# BaseModule.net
KiCad netlist of a schematic drawn in EAGLE
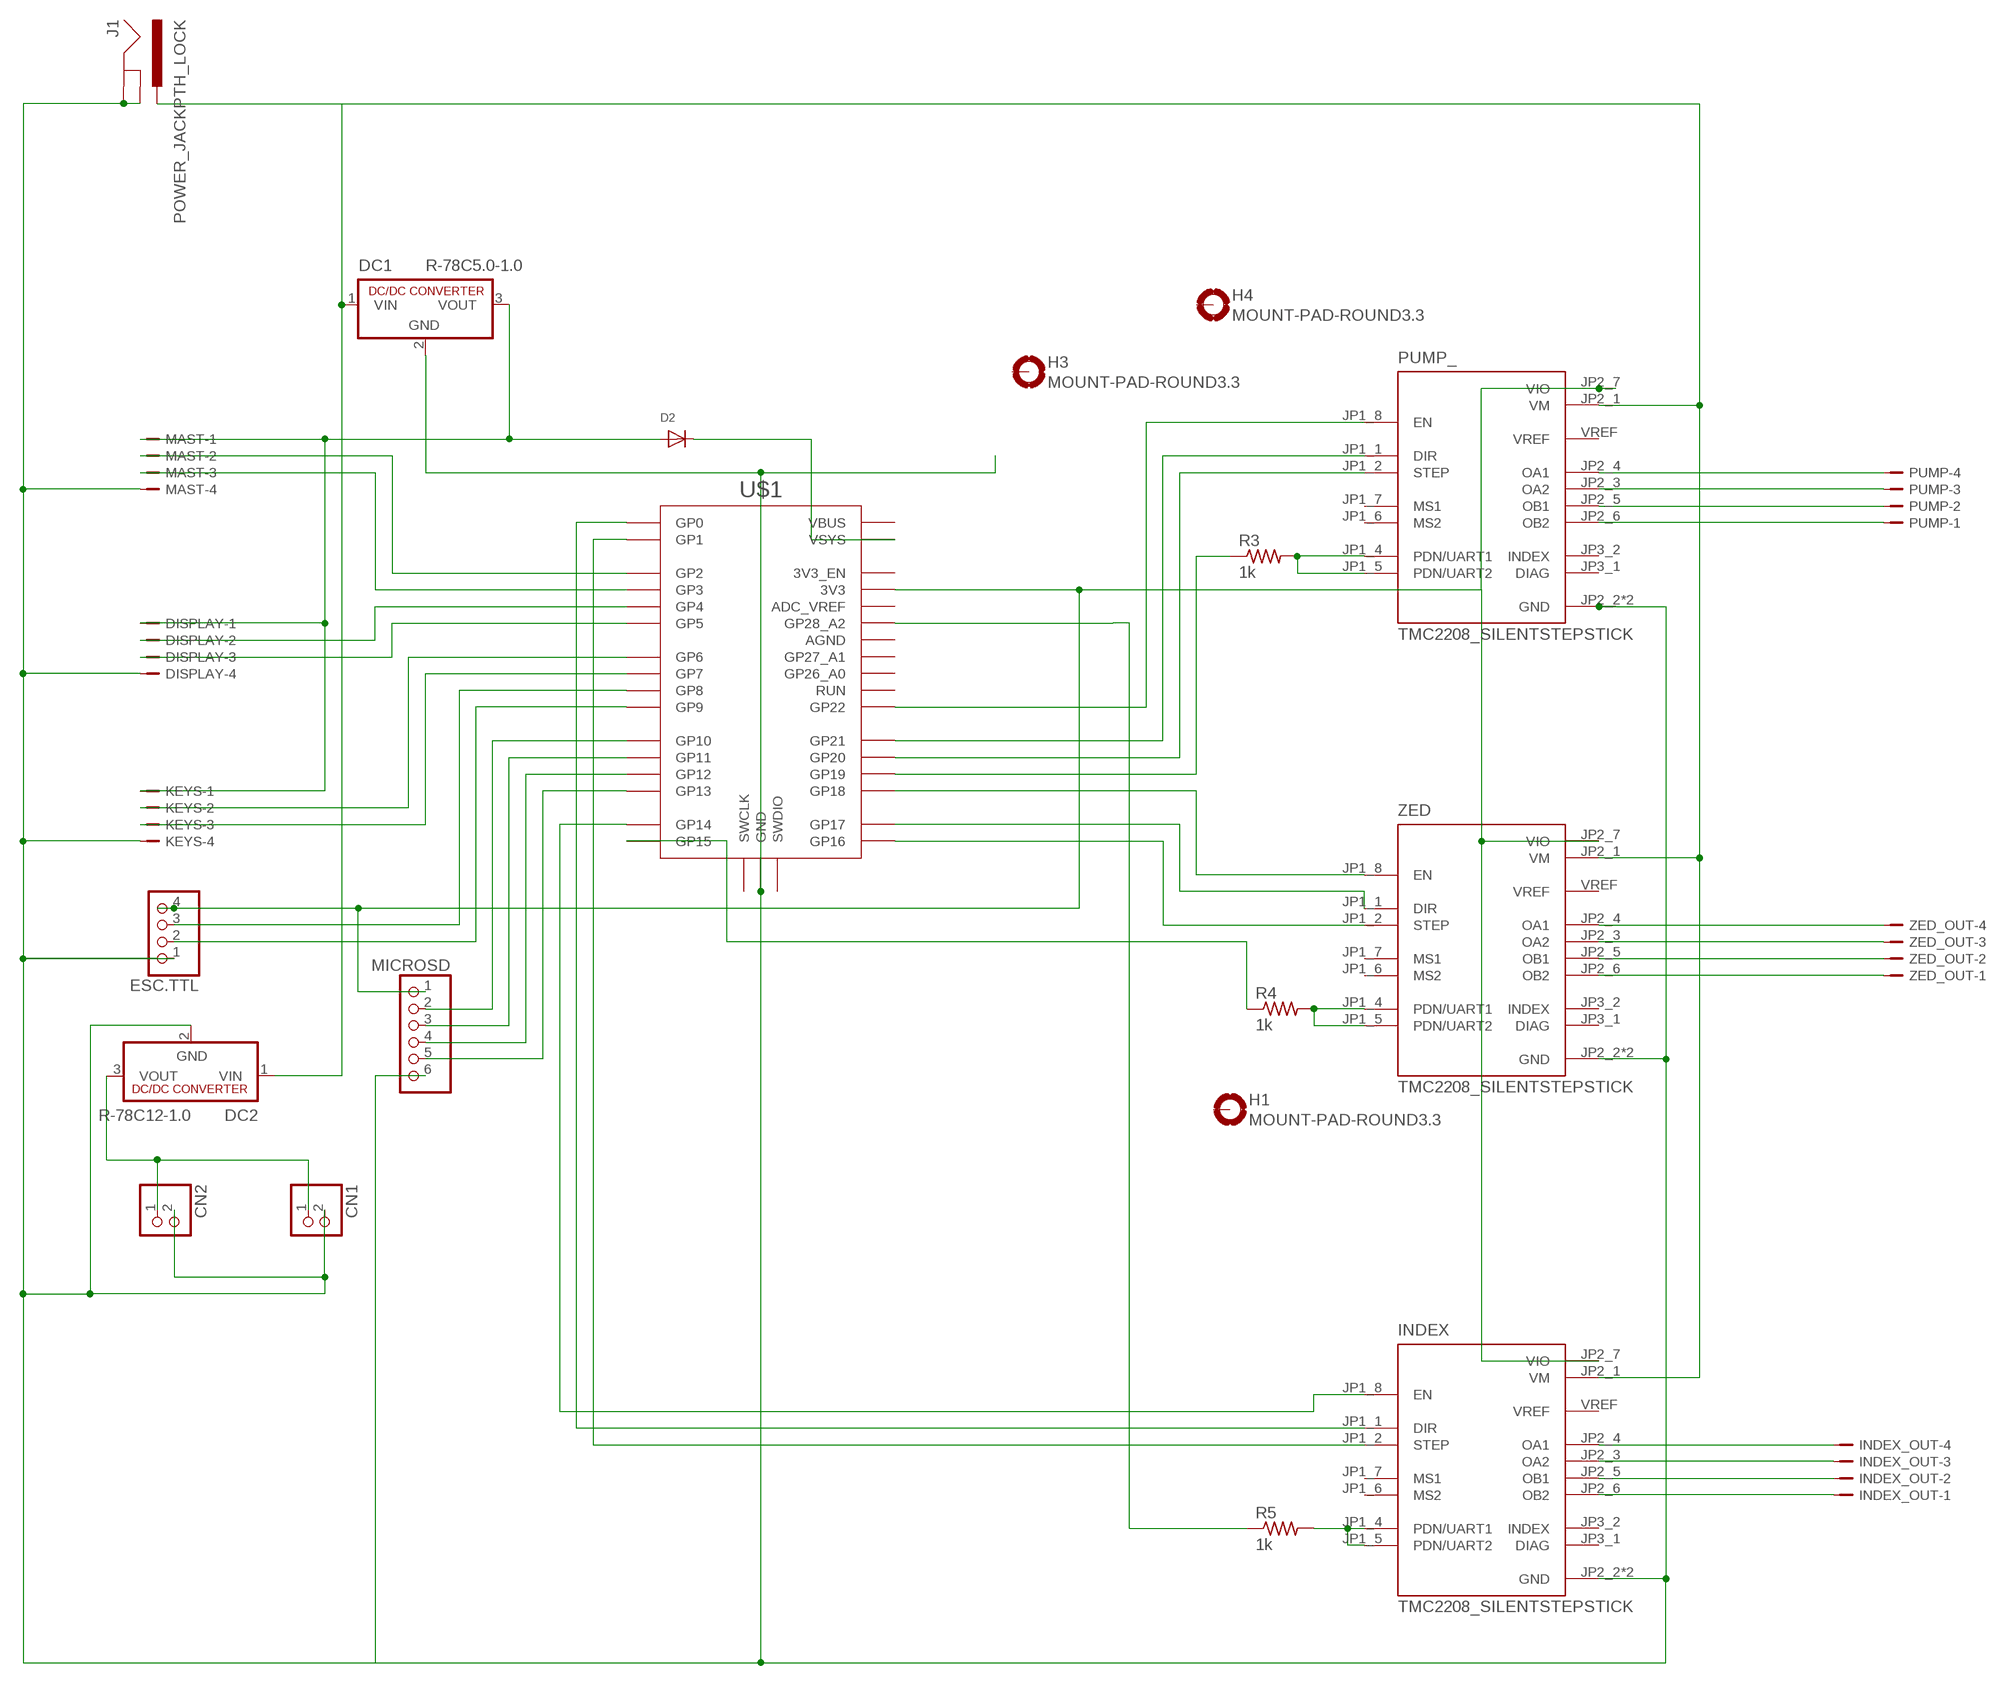
[diagram p0: schematic, sheet 1]

(export (version "E")
  (design (tool "Eeschema 10.0.6"))
  (components
    (comp (ref "CN1")
      (value "JST_2PIN-THM-RA")
      (footprint "eagle-import:JST-PH-2-THM-RA")
      (libsource (lib "eagle-import") (part "JST_2PIN-THM-RA"))
    )
    (comp (ref "CN2")
      (value "JST_2PIN-THM-RA")
      (footprint "eagle-import:JST-PH-2-THM-RA")
      (libsource (lib "eagle-import") (part "JST_2PIN-THM-RA"))
    )
    (comp (ref "D2")
      (value "DIODESMA")
      (footprint "eagle-import:SMADIODE")
      (libsource (lib "eagle-import") (part "DIODESMA"))
    )
    (comp (ref "DC1")
      (value "R-78C5.0-1.0")
      (footprint "eagle-import:SIP3")
      (libsource (lib "eagle-import") (part "R-78C-1.05.0"))
    )
    (comp (ref "DC2")
      (value "R-78C12-1.0")
      (footprint "eagle-import:SIP3")
      (libsource (lib "eagle-import") (part "R-78C-1.012"))
    )
    (comp (ref "DISPLAY")
      (value "JST-PH-4_TH-V")
      (footprint "eagle-import:B4B-PH-K-S")
      (fields (field (name "MF") "JST") (field (name "MPN") "B4B-PH-K-S"))
      (libsource (lib "eagle-import") (part "JST-PH-4_TH-V"))
    )
    (comp (ref "ESC.TTL")
      (value "PINHD-1X4")
      (footprint "eagle-import:1X04")
      (libsource (lib "eagle-import") (part "PINHD-1X4"))
    )
    (comp (ref "H1")
      (value "MOUNT-PAD-ROUND3.3")
      (footprint "eagle-import:3,3-PAD")
      (libsource (lib "eagle-import") (part "MOUNT-PAD-ROUND3.3"))
    )
    (comp (ref "H3")
      (value "MOUNT-PAD-ROUND3.3")
      (footprint "eagle-import:3,3-PAD")
      (libsource (lib "eagle-import") (part "MOUNT-PAD-ROUND3.3"))
    )
    (comp (ref "H4")
      (value "MOUNT-PAD-ROUND3.3")
      (footprint "eagle-import:3,3-PAD")
      (libsource (lib "eagle-import") (part "MOUNT-PAD-ROUND3.3"))
    )
    (comp (ref "INDEX")
      (value "TMC2208_SILENTSTEPSTICK")
      (footprint "eagle-import:MODULE_TMC2208_SILENTSTEPSTICK")
      (fields (field (name "MF") "Trinamic Motion") (field (name "MP") "TMC2208 SILENTSTEPSTICK"))
      (libsource (lib "eagle-import") (part "TMC2208_SILENTSTEPSTICK"))
    )
    (comp (ref "INDEX_OUT")
      (value "JST-PH-4_TH-RA")
      (footprint "eagle-import:S4B-PH-KL")
      (fields (field (name "MF") "JST") (field (name "MPN") "S4B-PH-KL"))
      (libsource (lib "eagle-import") (part "JST-PH-4_TH-RA"))
    )
    (comp (ref "J1")
      (value "POWER_JACKPTH_LOCK")
      (footprint "eagle-import:POWER_JACK_PTH_LOCK")
      (libsource (lib "eagle-import") (part "POWER_JACKPTH_LOCK"))
    )
    (comp (ref "KEYS")
      (value "JST-PH-4_TH-V")
      (footprint "eagle-import:B4B-PH-K-S")
      (fields (field (name "MF") "JST") (field (name "MPN") "B4B-PH-K-S"))
      (libsource (lib "eagle-import") (part "JST-PH-4_TH-V"))
    )
    (comp (ref "MAST")
      (value "JST-PH-4_TH-V")
      (footprint "eagle-import:B4B-PH-K-S")
      (fields (field (name "MF") "JST") (field (name "MPN") "B4B-PH-K-S"))
      (libsource (lib "eagle-import") (part "JST-PH-4_TH-V"))
    )
    (comp (ref "MICROSD")
      (value "PINHD-1X6")
      (footprint "eagle-import:1X06")
      (libsource (lib "eagle-import") (part "PINHD-1X6"))
    )
    (comp (ref "PUMP")
      (value "JST-PH-4_TH-RA")
      (footprint "eagle-import:S4B-PH-KL")
      (fields (field (name "MF") "JST") (field (name "MPN") "S4B-PH-KL"))
      (libsource (lib "eagle-import") (part "JST-PH-4_TH-RA"))
    )
    (comp (ref "PUMP_")
      (value "TMC2208_SILENTSTEPSTICK")
      (footprint "eagle-import:MODULE_TMC2208_SILENTSTEPSTICK")
      (fields (field (name "MF") "Trinamic Motion") (field (name "MP") "TMC2208 SILENTSTEPSTICK"))
      (libsource (lib "eagle-import") (part "TMC2208_SILENTSTEPSTICK"))
    )
    (comp (ref "R3")
      (value "1k")
      (footprint "eagle-import:R1206")
      (libsource (lib "eagle-import") (part "R-US_R1206"))
    )
    (comp (ref "R4")
      (value "1k")
      (footprint "eagle-import:R1206")
      (libsource (lib "eagle-import") (part "R-US_R1206"))
    )
    (comp (ref "R5")
      (value "1k")
      (footprint "eagle-import:R1206")
      (libsource (lib "eagle-import") (part "R-US_R1206"))
    )
    (comp (ref "U$1")
      (value "RPI_PICO-TH")
      (footprint "eagle-import:RPI_PICO_TH")
      (libsource (lib "eagle-import") (part "RPI_PICO-TH"))
    )
    (comp (ref "ZED")
      (value "TMC2208_SILENTSTEPSTICK")
      (footprint "eagle-import:MODULE_TMC2208_SILENTSTEPSTICK")
      (fields (field (name "MF") "Trinamic Motion") (field (name "MP") "TMC2208 SILENTSTEPSTICK"))
      (libsource (lib "eagle-import") (part "TMC2208_SILENTSTEPSTICK"))
    )
    (comp (ref "ZED_OUT")
      (value "JST-PH-4_TH-RA")
      (footprint "eagle-import:S4B-PH-KL")
      (fields (field (name "MF") "JST") (field (name "MPN") "S4B-PH-KL"))
      (libsource (lib "eagle-import") (part "JST-PH-4_TH-RA"))
    )
  )
  (nets
    (net (code "1") (name "Net-(CN1-1)") (class "Default")
      (node (ref "CN1") (pin "2") (pinfunction "1_2") (pintype "passive"))
      (node (ref "CN2") (pin "2") (pinfunction "1_2") (pintype "passive"))
      (node (ref "DC1") (pin "2") (pinfunction "GND_2") (pintype "passive"))
      (node (ref "DC2") (pin "2") (pinfunction "GND_2") (pintype "passive"))
      (node (ref "DISPLAY") (pin "4") (pinfunction "1_4") (pintype "passive"))
      (node (ref "ESC.TTL") (pin "1") (pinfunction "1_1") (pintype "passive"))
      (node (ref "INDEX") (pin "JP2_2") (pinfunction "GND_JP2_2") (pintype "power_in"))
      (node (ref "INDEX") (pin "JP2_8") (pinfunction "GND_JP2_8") (pintype "power_in"))
      (node (ref "J1") (pin "GND") (pinfunction "GND_GND") (pintype "bidirectional"))
      (node (ref "J1") (pin "GNDBREAK") (pinfunction "GNDBREAK_GNDBREAK") (pintype "bidirectional"))
      (node (ref "KEYS") (pin "4") (pinfunction "1_4") (pintype "passive"))
      (node (ref "MAST") (pin "4") (pinfunction "1_4") (pintype "passive"))
      (node (ref "MICROSD") (pin "6") (pinfunction "6_6") (pintype "passive"))
      (node (ref "PUMP_") (pin "JP2_2") (pinfunction "GND_JP2_2") (pintype "power_in"))
      (node (ref "PUMP_") (pin "JP2_8") (pinfunction "GND_JP2_8") (pintype "power_in"))
      (node (ref "U$1") (pin "GND@1") (pinfunction "GND_GND@1") (pintype "bidirectional"))
      (node (ref "U$1") (pin "GND@2") (pinfunction "GND_GND@2") (pintype "bidirectional"))
      (node (ref "U$1") (pin "GND@3") (pinfunction "GND_GND@3") (pintype "bidirectional"))
      (node (ref "U$1") (pin "GND@4") (pinfunction "GND_GND@4") (pintype "bidirectional"))
      (node (ref "U$1") (pin "GND@5") (pinfunction "GND_GND@5") (pintype "bidirectional"))
      (node (ref "U$1") (pin "GND@6") (pinfunction "GND_GND@6") (pintype "bidirectional"))
      (node (ref "U$1") (pin "GND@7") (pinfunction "GND_GND@7") (pintype "bidirectional"))
      (node (ref "U$1") (pin "GND@8") (pinfunction "GND_GND@8") (pintype "bidirectional"))
      (node (ref "ZED") (pin "JP2_2") (pinfunction "GND_JP2_2") (pintype "power_in"))
      (node (ref "ZED") (pin "JP2_8") (pinfunction "GND_JP2_8") (pintype "power_in"))
    )
    (net (code "2") (name "Net-(CN1-2)") (class "Default")
      (node (ref "CN1") (pin "1") (pinfunction "2_1") (pintype "passive"))
      (node (ref "CN2") (pin "1") (pinfunction "2_1") (pintype "passive"))
      (node (ref "DC2") (pin "3") (pinfunction "VOUT_3") (pintype "passive"))
    )
    (net (code "3") (name "Net-(D2-PadC)") (class "Default")
      (node (ref "D2") (pin "C") (pinfunction "C_C") (pintype "passive"))
      (node (ref "U$1") (pin "VSYS") (pinfunction "VSYS_VSYS") (pintype "bidirectional"))
    )
    (net (code "4") (name "Net-(DC1-VIN)") (class "Default")
      (node (ref "DC1") (pin "1") (pinfunction "VIN_1") (pintype "passive"))
      (node (ref "DC2") (pin "1") (pinfunction "VIN_1") (pintype "passive"))
      (node (ref "INDEX") (pin "JP2_1") (pinfunction "VM_JP2_1") (pintype "power_in"))
      (node (ref "J1") (pin "PWR") (pinfunction "PWR_PWR") (pintype "bidirectional"))
      (node (ref "PUMP_") (pin "JP2_1") (pinfunction "VM_JP2_1") (pintype "power_in"))
      (node (ref "ZED") (pin "JP2_1") (pinfunction "VM_JP2_1") (pintype "power_in"))
    )
    (net (code "5") (name "Net-(DC1-VOUT)") (class "Default")
      (node (ref "D2") (pin "A") (pinfunction "A_A") (pintype "passive"))
      (node (ref "DC1") (pin "3") (pinfunction "VOUT_3") (pintype "passive"))
      (node (ref "DISPLAY") (pin "1") (pinfunction "1_1") (pintype "passive"))
      (node (ref "KEYS") (pin "1") (pinfunction "1_1") (pintype "passive"))
      (node (ref "MAST") (pin "1") (pinfunction "1_1") (pintype "passive"))
    )
    (net (code "6") (name "Net-(DISPLAYB-1)") (class "Default")
      (node (ref "DISPLAY") (pin "2") (pinfunction "1_2") (pintype "passive"))
      (node (ref "U$1") (pin "GP4") (pinfunction "GP4_GP4") (pintype "bidirectional"))
    )
    (net (code "7") (name "Net-(DISPLAYC-1)") (class "Default")
      (node (ref "DISPLAY") (pin "3") (pinfunction "1_3") (pintype "passive"))
      (node (ref "U$1") (pin "GP5") (pinfunction "GP5_GP5") (pintype "bidirectional"))
    )
    (net (code "8") (name "Net-(ESC.TTL-Pad2)") (class "Default")
      (node (ref "ESC.TTL") (pin "2") (pinfunction "2_2") (pintype "passive"))
      (node (ref "U$1") (pin "GP9") (pinfunction "GP9_GP9") (pintype "bidirectional"))
    )
    (net (code "9") (name "Net-(ESC.TTL-Pad3)") (class "Default")
      (node (ref "ESC.TTL") (pin "3") (pinfunction "3_3") (pintype "passive"))
      (node (ref "U$1") (pin "GP8") (pinfunction "GP8_GP8") (pintype "bidirectional"))
    )
    (net (code "10") (name "Net-(INDEX-DIR)") (class "Default")
      (node (ref "INDEX") (pin "JP1_1") (pinfunction "DIR_JP1_1") (pintype "input"))
      (node (ref "U$1") (pin "GP0") (pinfunction "GP0_GP0") (pintype "bidirectional"))
    )
    (net (code "11") (name "Net-(INDEX-EN)") (class "Default")
      (node (ref "INDEX") (pin "JP1_8") (pinfunction "EN_JP1_8") (pintype "input"))
      (node (ref "U$1") (pin "GP14") (pinfunction "GP14_GP14") (pintype "bidirectional"))
    )
    (net (code "12") (name "Net-(INDEX-OA1)") (class "Default")
      (node (ref "INDEX") (pin "JP2_4") (pinfunction "OA1_JP2_4") (pintype "passive"))
      (node (ref "INDEX_OUT") (pin "4") (pinfunction "1_4") (pintype "passive"))
    )
    (net (code "13") (name "Net-(INDEX-OA2)") (class "Default")
      (node (ref "INDEX") (pin "JP2_3") (pinfunction "OA2_JP2_3") (pintype "passive"))
      (node (ref "INDEX_OUT") (pin "3") (pinfunction "1_3") (pintype "passive"))
    )
    (net (code "14") (name "Net-(INDEX-OB1)") (class "Default")
      (node (ref "INDEX") (pin "JP2_5") (pinfunction "OB1_JP2_5") (pintype "passive"))
      (node (ref "INDEX_OUT") (pin "2") (pinfunction "1_2") (pintype "passive"))
    )
    (net (code "15") (name "Net-(INDEX-OB2)") (class "Default")
      (node (ref "INDEX") (pin "JP2_6") (pinfunction "OB2_JP2_6") (pintype "passive"))
      (node (ref "INDEX_OUT") (pin "1") (pinfunction "1_1") (pintype "passive"))
    )
    (net (code "16") (name "Net-(INDEX-PDN{slash}UART1)") (class "Default")
      (node (ref "INDEX") (pin "JP1_4") (pinfunction "PDN/UART1_JP1_4") (pintype "bidirectional"))
      (node (ref "INDEX") (pin "JP1_5") (pinfunction "PDN/UART2_JP1_5") (pintype "bidirectional"))
      (node (ref "R5") (pin "2") (pinfunction "2_2") (pintype "passive"))
    )
    (net (code "17") (name "Net-(INDEX-STEP)") (class "Default")
      (node (ref "INDEX") (pin "JP1_2") (pinfunction "STEP_JP1_2") (pintype "input"))
      (node (ref "U$1") (pin "GP1") (pinfunction "GP1_GP1") (pintype "bidirectional"))
    )
    (net (code "18") (name "Net-(INDEX-VIO)") (class "Default")
      (node (ref "ESC.TTL") (pin "4") (pinfunction "4_4") (pintype "passive"))
      (node (ref "INDEX") (pin "JP2_7") (pinfunction "VIO_JP2_7") (pintype "power_in"))
      (node (ref "MICROSD") (pin "1") (pinfunction "1_1") (pintype "passive"))
      (node (ref "PUMP_") (pin "JP2_7") (pinfunction "VIO_JP2_7") (pintype "power_in"))
      (node (ref "U$1") (pin "3V3") (pinfunction "3V3_3V3") (pintype "bidirectional"))
      (node (ref "ZED") (pin "JP2_7") (pinfunction "VIO_JP2_7") (pintype "power_in"))
    )
    (net (code "19") (name "Net-(KEYSB-1)") (class "Default")
      (node (ref "KEYS") (pin "2") (pinfunction "1_2") (pintype "passive"))
      (node (ref "U$1") (pin "GP6") (pinfunction "GP6_GP6") (pintype "bidirectional"))
    )
    (net (code "20") (name "Net-(KEYSC-1)") (class "Default")
      (node (ref "KEYS") (pin "3") (pinfunction "1_3") (pintype "passive"))
      (node (ref "U$1") (pin "GP7") (pinfunction "GP7_GP7") (pintype "bidirectional"))
    )
    (net (code "21") (name "Net-(MASTB-1)") (class "Default")
      (node (ref "MAST") (pin "2") (pinfunction "1_2") (pintype "passive"))
      (node (ref "U$1") (pin "GP2") (pinfunction "GP2_GP2") (pintype "bidirectional"))
    )
    (net (code "22") (name "Net-(MASTC-1)") (class "Default")
      (node (ref "MAST") (pin "3") (pinfunction "1_3") (pintype "passive"))
      (node (ref "U$1") (pin "GP3") (pinfunction "GP3_GP3") (pintype "bidirectional"))
    )
    (net (code "23") (name "Net-(MICROSD-Pad2)") (class "Default")
      (node (ref "MICROSD") (pin "2") (pinfunction "2_2") (pintype "passive"))
      (node (ref "U$1") (pin "GP10") (pinfunction "GP10_GP10") (pintype "bidirectional"))
    )
    (net (code "24") (name "Net-(MICROSD-Pad3)") (class "Default")
      (node (ref "MICROSD") (pin "3") (pinfunction "3_3") (pintype "passive"))
      (node (ref "U$1") (pin "GP11") (pinfunction "GP11_GP11") (pintype "bidirectional"))
    )
    (net (code "25") (name "Net-(MICROSD-Pad4)") (class "Default")
      (node (ref "MICROSD") (pin "4") (pinfunction "4_4") (pintype "passive"))
      (node (ref "U$1") (pin "GP12") (pinfunction "GP12_GP12") (pintype "bidirectional"))
    )
    (net (code "26") (name "Net-(MICROSD-Pad5)") (class "Default")
      (node (ref "MICROSD") (pin "5") (pinfunction "5_5") (pintype "passive"))
      (node (ref "U$1") (pin "GP13") (pinfunction "GP13_GP13") (pintype "bidirectional"))
    )
    (net (code "27") (name "Net-(PUMPB-1)") (class "Default")
      (node (ref "PUMP") (pin "2") (pinfunction "1_2") (pintype "passive"))
      (node (ref "PUMP_") (pin "JP2_5") (pinfunction "OB1_JP2_5") (pintype "passive"))
    )
    (net (code "28") (name "Net-(PUMPC-1)") (class "Default")
      (node (ref "PUMP") (pin "3") (pinfunction "1_3") (pintype "passive"))
      (node (ref "PUMP_") (pin "JP2_3") (pinfunction "OA2_JP2_3") (pintype "passive"))
    )
    (net (code "29") (name "Net-(PUMPD-1)") (class "Default")
      (node (ref "PUMP") (pin "4") (pinfunction "1_4") (pintype "passive"))
      (node (ref "PUMP_") (pin "JP2_4") (pinfunction "OA1_JP2_4") (pintype "passive"))
    )
    (net (code "30") (name "Net-(PUMP_-DIR)") (class "Default")
      (node (ref "PUMP_") (pin "JP1_1") (pinfunction "DIR_JP1_1") (pintype "input"))
      (node (ref "U$1") (pin "GP21") (pinfunction "GP21_GP21") (pintype "bidirectional"))
    )
    (net (code "31") (name "Net-(PUMP_-EN)") (class "Default")
      (node (ref "PUMP_") (pin "JP1_8") (pinfunction "EN_JP1_8") (pintype "input"))
      (node (ref "U$1") (pin "GP22") (pinfunction "GP22_GP22") (pintype "bidirectional"))
    )
    (net (code "32") (name "Net-(PUMP_-OB2)") (class "Default")
      (node (ref "PUMP") (pin "1") (pinfunction "1_1") (pintype "passive"))
      (node (ref "PUMP_") (pin "JP2_6") (pinfunction "OB2_JP2_6") (pintype "passive"))
    )
    (net (code "33") (name "Net-(PUMP_-PDN{slash}UART1)") (class "Default")
      (node (ref "PUMP_") (pin "JP1_4") (pinfunction "PDN/UART1_JP1_4") (pintype "bidirectional"))
      (node (ref "PUMP_") (pin "JP1_5") (pinfunction "PDN/UART2_JP1_5") (pintype "bidirectional"))
      (node (ref "R3") (pin "2") (pinfunction "2_2") (pintype "passive"))
    )
    (net (code "34") (name "Net-(PUMP_-STEP)") (class "Default")
      (node (ref "PUMP_") (pin "JP1_2") (pinfunction "STEP_JP1_2") (pintype "input"))
      (node (ref "U$1") (pin "GP20") (pinfunction "GP20_GP20") (pintype "bidirectional"))
    )
    (net (code "35") (name "Net-(R3-Pad1)") (class "Default")
      (node (ref "R3") (pin "1") (pinfunction "1_1") (pintype "passive"))
      (node (ref "U$1") (pin "GP19") (pinfunction "GP19_GP19") (pintype "bidirectional"))
    )
    (net (code "36") (name "Net-(R4-Pad1)") (class "Default")
      (node (ref "R4") (pin "1") (pinfunction "1_1") (pintype "passive"))
      (node (ref "U$1") (pin "GP15") (pinfunction "GP15_GP15") (pintype "bidirectional"))
    )
    (net (code "37") (name "Net-(R5-Pad1)") (class "Default")
      (node (ref "R5") (pin "1") (pinfunction "1_1") (pintype "passive"))
      (node (ref "U$1") (pin "GP28_A2") (pinfunction "GP28_A2_GP28_A2") (pintype "bidirectional"))
    )
    (net (code "38") (name "Net-(ZED-DIR)") (class "Default")
      (node (ref "U$1") (pin "GP17") (pinfunction "GP17_GP17") (pintype "bidirectional"))
      (node (ref "ZED") (pin "JP1_1") (pinfunction "DIR_JP1_1") (pintype "input"))
    )
    (net (code "39") (name "Net-(ZED-EN)") (class "Default")
      (node (ref "U$1") (pin "GP18") (pinfunction "GP18_GP18") (pintype "bidirectional"))
      (node (ref "ZED") (pin "JP1_8") (pinfunction "EN_JP1_8") (pintype "input"))
    )
    (net (code "40") (name "Net-(ZED-OA1)") (class "Default")
      (node (ref "ZED") (pin "JP2_4") (pinfunction "OA1_JP2_4") (pintype "passive"))
      (node (ref "ZED_OUT") (pin "4") (pinfunction "1_4") (pintype "passive"))
    )
    (net (code "41") (name "Net-(ZED-OA2)") (class "Default")
      (node (ref "ZED") (pin "JP2_3") (pinfunction "OA2_JP2_3") (pintype "passive"))
      (node (ref "ZED_OUT") (pin "3") (pinfunction "1_3") (pintype "passive"))
    )
    (net (code "42") (name "Net-(ZED-OB1)") (class "Default")
      (node (ref "ZED") (pin "JP2_5") (pinfunction "OB1_JP2_5") (pintype "passive"))
      (node (ref "ZED_OUT") (pin "2") (pinfunction "1_2") (pintype "passive"))
    )
    (net (code "43") (name "Net-(ZED-OB2)") (class "Default")
      (node (ref "ZED") (pin "JP2_6") (pinfunction "OB2_JP2_6") (pintype "passive"))
      (node (ref "ZED_OUT") (pin "1") (pinfunction "1_1") (pintype "passive"))
    )
    (net (code "44") (name "Net-(ZED-PDN{slash}UART1)") (class "Default")
      (node (ref "R4") (pin "2") (pinfunction "2_2") (pintype "passive"))
      (node (ref "ZED") (pin "JP1_4") (pinfunction "PDN/UART1_JP1_4") (pintype "bidirectional"))
      (node (ref "ZED") (pin "JP1_5") (pinfunction "PDN/UART2_JP1_5") (pintype "bidirectional"))
    )
    (net (code "45") (name "Net-(ZED-STEP)") (class "Default")
      (node (ref "U$1") (pin "GP16") (pinfunction "GP16_GP16") (pintype "bidirectional"))
      (node (ref "ZED") (pin "JP1_2") (pinfunction "STEP_JP1_2") (pintype "input"))
    )
    (net (code "46") (name "unconnected-(H1-MOUNT-PadB3,3)") (class "Default")
      (node (ref "H1") (pin "B3,3") (pinfunction "MOUNT_B3,3") (pintype "passive"))
    )
    (net (code "47") (name "unconnected-(H3-MOUNT-PadB3,3)") (class "Default")
      (node (ref "H3") (pin "B3,3") (pinfunction "MOUNT_B3,3") (pintype "passive"))
    )
    (net (code "48") (name "unconnected-(H4-MOUNT-PadB3,3)") (class "Default")
      (node (ref "H4") (pin "B3,3") (pinfunction "MOUNT_B3,3") (pintype "passive"))
    )
    (net (code "49") (name "unconnected-(INDEX-DIAG-PadJP3_1)") (class "Default")
      (node (ref "INDEX") (pin "JP3_1") (pinfunction "DIAG_JP3_1") (pintype "output"))
    )
    (net (code "50") (name "unconnected-(INDEX-INDEX-PadJP3_2)") (class "Default")
      (node (ref "INDEX") (pin "JP3_2") (pinfunction "INDEX_JP3_2") (pintype "output"))
    )
    (net (code "51") (name "unconnected-(INDEX-MS1-PadJP1_7)") (class "Default")
      (node (ref "INDEX") (pin "JP1_7") (pinfunction "MS1_JP1_7") (pintype "input"))
    )
    (net (code "52") (name "unconnected-(INDEX-MS2-PadJP1_6)") (class "Default")
      (node (ref "INDEX") (pin "JP1_6") (pinfunction "MS2_JP1_6") (pintype "input"))
    )
    (net (code "53") (name "unconnected-(INDEX-PadVREF)") (class "Default")
      (node (ref "INDEX") (pin "VREF") (pinfunction "VREF_VREF") (pintype "passive"))
    )
    (net (code "54") (name "unconnected-(PUMP_-DIAG-PadJP3_1)") (class "Default")
      (node (ref "PUMP_") (pin "JP3_1") (pinfunction "DIAG_JP3_1") (pintype "output"))
    )
    (net (code "55") (name "unconnected-(PUMP_-INDEX-PadJP3_2)") (class "Default")
      (node (ref "PUMP_") (pin "JP3_2") (pinfunction "INDEX_JP3_2") (pintype "output"))
    )
    (net (code "56") (name "unconnected-(PUMP_-MS1-PadJP1_7)") (class "Default")
      (node (ref "PUMP_") (pin "JP1_7") (pinfunction "MS1_JP1_7") (pintype "input"))
    )
    (net (code "57") (name "unconnected-(PUMP_-MS2-PadJP1_6)") (class "Default")
      (node (ref "PUMP_") (pin "JP1_6") (pinfunction "MS2_JP1_6") (pintype "input"))
    )
    (net (code "58") (name "unconnected-(PUMP_-PadVREF)") (class "Default")
      (node (ref "PUMP_") (pin "VREF") (pinfunction "VREF_VREF") (pintype "passive"))
    )
    (net (code "59") (name "unconnected-(U$1-Pad3V3_EN)") (class "Default")
      (node (ref "U$1") (pin "3V3_EN") (pinfunction "3V3_EN_3V3_EN") (pintype "bidirectional"))
    )
    (net (code "60") (name "unconnected-(U$1-PadADC_VREF)") (class "Default")
      (node (ref "U$1") (pin "ADC_VREF") (pinfunction "ADC_VREF_ADC_VREF") (pintype "bidirectional"))
    )
    (net (code "61") (name "unconnected-(U$1-PadAGND)") (class "Default")
      (node (ref "U$1") (pin "AGND") (pinfunction "AGND_AGND") (pintype "bidirectional"))
    )
    (net (code "62") (name "unconnected-(U$1-PadGP26_A0)") (class "Default")
      (node (ref "U$1") (pin "GP26_A0") (pinfunction "GP26_A0_GP26_A0") (pintype "bidirectional"))
    )
    (net (code "63") (name "unconnected-(U$1-PadGP27_A1)") (class "Default")
      (node (ref "U$1") (pin "GP27_A1") (pinfunction "GP27_A1_GP27_A1") (pintype "bidirectional"))
    )
    (net (code "64") (name "unconnected-(U$1-PadRUN)") (class "Default")
      (node (ref "U$1") (pin "RUN") (pinfunction "RUN_RUN") (pintype "bidirectional"))
    )
    (net (code "65") (name "unconnected-(U$1-PadSWCLK)") (class "Default")
      (node (ref "U$1") (pin "SWCLK") (pinfunction "SWCLK_SWCLK") (pintype "bidirectional"))
    )
    (net (code "66") (name "unconnected-(U$1-PadSWDIO)") (class "Default")
      (node (ref "U$1") (pin "SWDIO") (pinfunction "SWDIO_SWDIO") (pintype "bidirectional"))
    )
    (net (code "67") (name "unconnected-(U$1-PadVBUS)") (class "Default")
      (node (ref "U$1") (pin "VBUS") (pinfunction "VBUS_VBUS") (pintype "bidirectional"))
    )
    (net (code "68") (name "unconnected-(ZED-DIAG-PadJP3_1)") (class "Default")
      (node (ref "ZED") (pin "JP3_1") (pinfunction "DIAG_JP3_1") (pintype "output"))
    )
    (net (code "69") (name "unconnected-(ZED-INDEX-PadJP3_2)") (class "Default")
      (node (ref "ZED") (pin "JP3_2") (pinfunction "INDEX_JP3_2") (pintype "output"))
    )
    (net (code "70") (name "unconnected-(ZED-MS1-PadJP1_7)") (class "Default")
      (node (ref "ZED") (pin "JP1_7") (pinfunction "MS1_JP1_7") (pintype "input"))
    )
    (net (code "71") (name "unconnected-(ZED-MS2-PadJP1_6)") (class "Default")
      (node (ref "ZED") (pin "JP1_6") (pinfunction "MS2_JP1_6") (pintype "input"))
    )
    (net (code "72") (name "unconnected-(ZED-PadVREF)") (class "Default")
      (node (ref "ZED") (pin "VREF") (pinfunction "VREF_VREF") (pintype "passive"))
    )
  )
)
